# 00_POWER.net
KiCad netlist of a schematic drawn in Altium Designer
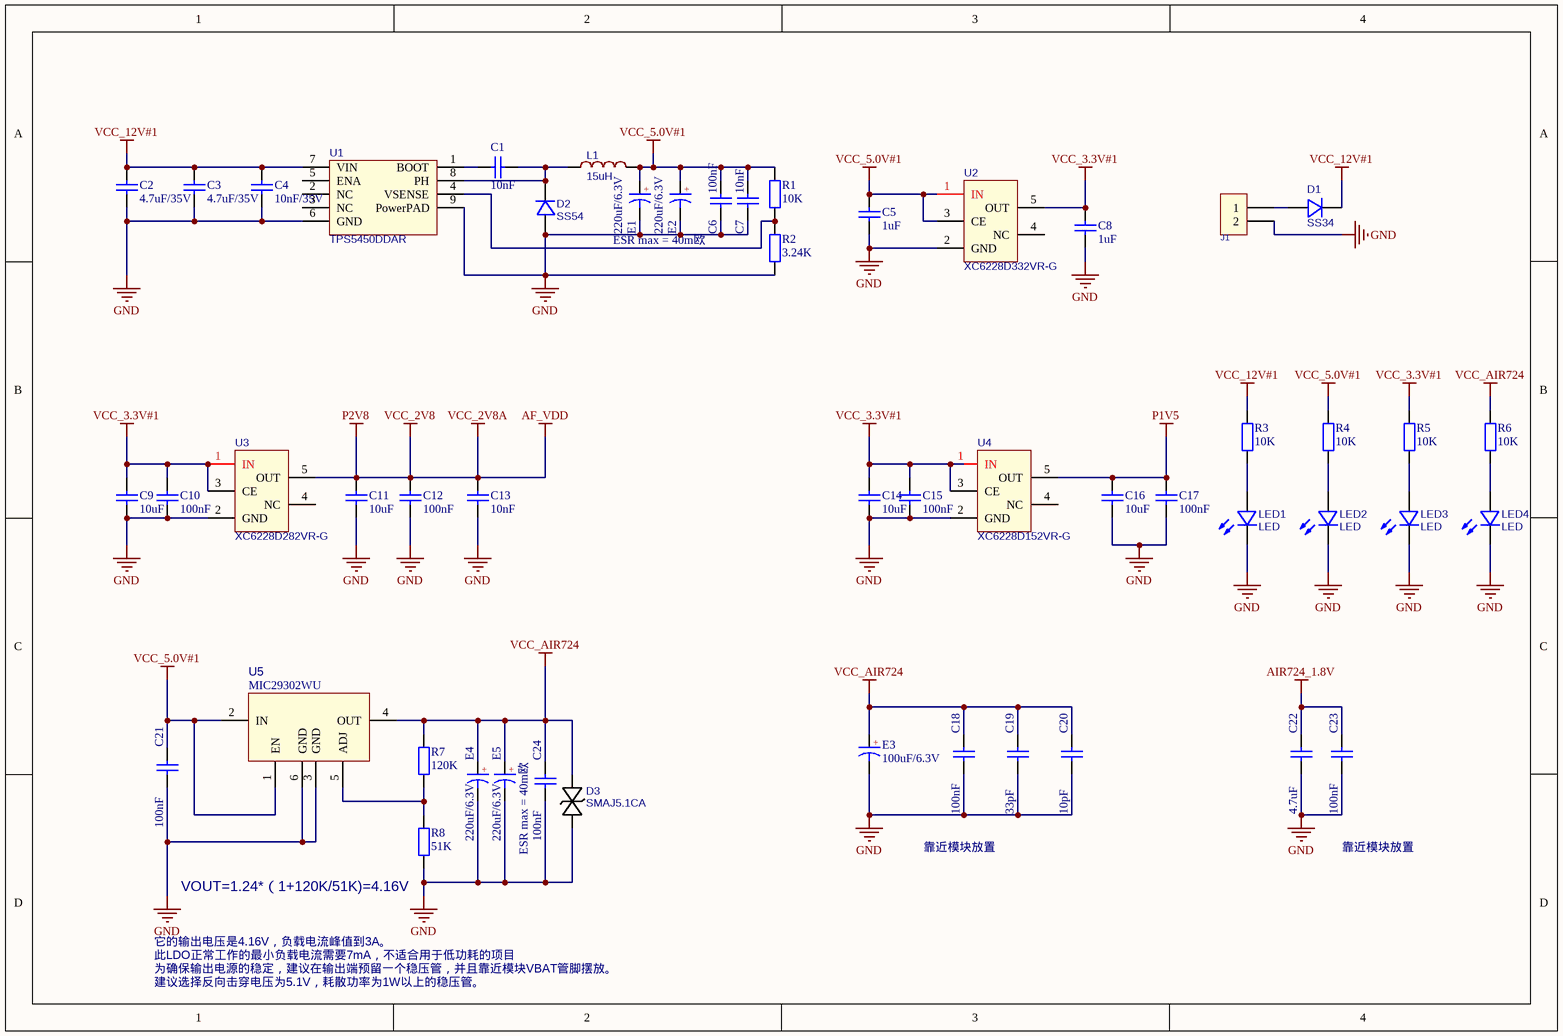
[diagram p0: 00_POWER.SchDoc]

(export (version "E")
  (design (tool "Eeschema 10.0.6"))
  (components
    (comp (ref "C1")
      (value "10nF")
      (footprint "0603-C")
      (description "贴片电容")
      (libsource (lib "封装库") (part "C"))
    )
    (comp (ref "C2")
      (value "4.7uF/35V")
      (footprint "0805-C")
      (description "贴片电容")
      (libsource (lib "封装库") (part "C"))
    )
    (comp (ref "C3")
      (value "4.7uF/35V")
      (footprint "0805-C")
      (description "贴片电容")
      (libsource (lib "封装库") (part "C"))
    )
    (comp (ref "C4")
      (value "10nF/35V")
      (footprint "0603-C")
      (description "贴片电容")
      (libsource (lib "封装库") (part "C"))
    )
    (comp (ref "C5")
      (value "1uF")
      (footprint "0603-C")
      (description "贴片电容")
      (libsource (lib "封装库") (part "C"))
    )
    (comp (ref "C6")
      (value "100nF")
      (footprint "0603-C")
      (description "贴片电容")
      (libsource (lib "封装库") (part "C"))
    )
    (comp (ref "C7")
      (value "10nF")
      (footprint "0603-C")
      (description "贴片电容")
      (libsource (lib "封装库") (part "C"))
    )
    (comp (ref "C8")
      (value "1uF")
      (footprint "0603-C")
      (description "贴片电容")
      (libsource (lib "封装库") (part "C"))
    )
    (comp (ref "C9")
      (value "10uF")
      (footprint "0603-C")
      (description "贴片电容")
      (libsource (lib "封装库") (part "C"))
    )
    (comp (ref "C10")
      (value "100nF")
      (footprint "0603-C")
      (description "贴片电容")
      (libsource (lib "封装库") (part "C"))
    )
    (comp (ref "C11")
      (value "10uF")
      (footprint "0603-C")
      (description "贴片电容")
      (libsource (lib "封装库") (part "C"))
    )
    (comp (ref "C12")
      (value "100nF")
      (footprint "0603-C")
      (description "贴片电容")
      (libsource (lib "封装库") (part "C"))
    )
    (comp (ref "C13")
      (value "10nF")
      (footprint "0603-C")
      (description "贴片电容")
      (libsource (lib "封装库") (part "C"))
    )
    (comp (ref "C14")
      (value "10uF")
      (footprint "0603-C")
      (description "贴片电容")
      (libsource (lib "封装库") (part "C"))
    )
    (comp (ref "C15")
      (value "100nF")
      (footprint "0603-C")
      (description "贴片电容")
      (libsource (lib "封装库") (part "C"))
    )
    (comp (ref "C16")
      (value "10uF")
      (footprint "0603-C")
      (description "贴片电容")
      (libsource (lib "封装库") (part "C"))
    )
    (comp (ref "C17")
      (value "100nF")
      (footprint "0603-C")
      (description "贴片电容")
      (libsource (lib "封装库") (part "C"))
    )
    (comp (ref "C18")
      (value "100nF")
      (footprint "0603-C")
      (description "贴片电容")
      (libsource (lib "封装库") (part "C"))
    )
    (comp (ref "C19")
      (value "33pF")
      (footprint "0603-C")
      (description "贴片电容")
      (libsource (lib "封装库") (part "C"))
    )
    (comp (ref "C20")
      (value "10pF")
      (footprint "0603-C")
      (description "贴片电容")
      (libsource (lib "封装库") (part "C"))
    )
    (comp (ref "C21")
      (value "100nF")
      (footprint "0603-C")
      (description "贴片电容")
      (libsource (lib "封装库") (part "C"))
    )
    (comp (ref "C22")
      (value "4.7uF")
      (footprint "0603-C")
      (description "贴片电容")
      (libsource (lib "封装库") (part "C"))
    )
    (comp (ref "C23")
      (value "100nF")
      (footprint "0603-C")
      (description "贴片电容")
      (libsource (lib "封装库") (part "C"))
    )
    (comp (ref "C24")
      (value "100nF")
      (footprint "0603-C")
      (description "贴片电容")
      (libsource (lib "封装库") (part "C"))
    )
    (comp (ref "D1")
      (value "SS34")
      (footprint "SS34-SMA")
      (fields
        (field (name "BOM_SUPPLIER PART") "C118334")
        (field (name "BOM_MANUFACTURER PART") "D-G060306G1-KS2")
        (field (name "CONTRIBUTOR") "LCSC")
      )
      (libsource (lib "封装库") (part "SS34"))
    )
    (comp (ref "D2")
      (value "SS54")
      (footprint "SS34-SMA")
      (fields
        (field (name "BOM_SUPPLIER PART") "C118334")
        (field (name "BOM_MANUFACTURER PART") "D-G060306G1-KS2")
        (field (name "CONTRIBUTOR") "LCSC")
      )
      (libsource (lib "封装库") (part "SS34"))
    )
    (comp (ref "D3")
      (value "SMAJ5.1CA")
      (footprint "ZENER")
      (description "SMAJ6.0CA_C698928")
      (fields
        (field (name "BOM_SUPPLIER PART") "C698928")
        (field (name "BOM_MANUFACTURER PART") "SMAJ6.0CA")
        (field (name "CONTRIBUTOR") "LCSC")
      )
      (libsource (lib "封装库") (part "SMAJ6.0CA"))
    )
    (comp (ref "E1")
      (value "220uF/6.3V")
      (footprint "CD B(3528)")
      (description "贴片钽电容")
      (libsource (lib "封装库") (part "CT"))
    )
    (comp (ref "E2")
      (value "220uF/6.3V")
      (footprint "CD B(3528)")
      (description "贴片钽电容")
      (libsource (lib "封装库") (part "CT"))
    )
    (comp (ref "E3")
      (value "100uF/6.3V")
      (footprint "CD B(3528)")
      (description "贴片钽电容")
      (libsource (lib "封装库") (part "CT"))
    )
    (comp (ref "E4")
      (value "220uF/6.3V")
      (footprint "CD B(3528)")
      (description "贴片钽电容")
      (libsource (lib "封装库") (part "CT"))
    )
    (comp (ref "E5")
      (value "220uF/6.3V")
      (footprint "CD B(3528)")
      (description "贴片钽电容")
      (libsource (lib "封装库") (part "CT"))
    )
    (comp (ref "J1")
      (value "KF128-5.0-2P")
      (footprint "KF128-5.0-2P")
      (fields (field (name "MANUFACTURER") "KEFA(科发)"))
      (libsource (lib "封装库") (part "KF128-5.0-2P"))
    )
    (comp (ref "L1")
      (value "15uH")
      (footprint "电感7*7*3")
      (description "L")
      (fields
        (field (name "BOM_MANUFACTURER PART") "UPZ2012D800-4R0TF")
        (field (name "BOM_SUPPLIER PART") "C145060")
        (field (name "CONTRIBUTOR") "LCSC")
      )
      (libsource (lib "封装库") (part "L"))
    )
    (comp (ref "LED1")
      (value "LED")
      (footprint "LED-0603")
      (fields
        (field (name "BOM_SUPPLIER PART") "C118334")
        (field (name "BOM_MANUFACTURER PART") "D-G060306G1-KS2")
        (field (name "CONTRIBUTOR") "LCSC")
      )
      (libsource (lib "封装库") (part "LED"))
    )
    (comp (ref "LED2")
      (value "LED")
      (footprint "LED-0603")
      (fields
        (field (name "BOM_SUPPLIER PART") "C118334")
        (field (name "BOM_MANUFACTURER PART") "D-G060306G1-KS2")
        (field (name "CONTRIBUTOR") "LCSC")
      )
      (libsource (lib "封装库") (part "LED"))
    )
    (comp (ref "LED3")
      (value "LED")
      (footprint "LED-0603")
      (fields
        (field (name "BOM_SUPPLIER PART") "C118334")
        (field (name "BOM_MANUFACTURER PART") "D-G060306G1-KS2")
        (field (name "CONTRIBUTOR") "LCSC")
      )
      (libsource (lib "封装库") (part "LED"))
    )
    (comp (ref "LED4")
      (value "LED")
      (footprint "LED-0603")
      (fields
        (field (name "BOM_SUPPLIER PART") "C118334")
        (field (name "BOM_MANUFACTURER PART") "D-G060306G1-KS2")
        (field (name "CONTRIBUTOR") "LCSC")
      )
      (libsource (lib "封装库") (part "LED"))
    )
    (comp (ref "R1")
      (value "10K")
      (footprint "0603-R")
      (description "贴片电阻")
      (libsource (lib "封装库") (part "R"))
    )
    (comp (ref "R2")
      (value "3.24K")
      (footprint "0603-R")
      (description "贴片电阻")
      (libsource (lib "封装库") (part "R"))
    )
    (comp (ref "R3")
      (value "10K")
      (footprint "0603-R")
      (description "贴片电阻")
      (libsource (lib "封装库") (part "R"))
    )
    (comp (ref "R4")
      (value "10K")
      (footprint "0603-R")
      (description "贴片电阻")
      (libsource (lib "封装库") (part "R"))
    )
    (comp (ref "R5")
      (value "10K")
      (footprint "0603-R")
      (description "贴片电阻")
      (libsource (lib "封装库") (part "R"))
    )
    (comp (ref "R6")
      (value "10K")
      (footprint "0603-R")
      (description "贴片电阻")
      (libsource (lib "封装库") (part "R"))
    )
    (comp (ref "R7")
      (value "120K")
      (footprint "0603-R")
      (description "贴片电阻")
      (libsource (lib "封装库") (part "R"))
    )
    (comp (ref "R8")
      (value "51K")
      (footprint "0603-R")
      (description "贴片电阻")
      (libsource (lib "封装库") (part "R"))
    )
    (comp (ref "U1")
      (value "TPS5450DDAR")
      (footprint "TPS5430")
      (fields (field (name "BOM_MANUFACTURER PART") "TPS5430DDAR") (field (name "BOM_SUPPLIER PART") "C9864"))
      (libsource (lib "封装库") (part "TPS5430DDAR"))
    )
    (comp (ref "U2")
      (value "XC6228D332VR-G")
      (footprint "XC6228D332VR-G")
      (fields (field (name "BOM_SUPPLIER PART") "C69841"))
      (libsource (lib "封装库") (part "XC6228D332VR-G"))
    )
    (comp (ref "U3")
      (value "XC6228D282VR-G")
      (footprint "XC6228D332VR-G")
      (fields
        (field (name "BOM_MANUFACTURER PART") "XC6228D332VR-G")
        (field (name "BOM_SUPPLIER PART") "C69841")
      )
      (libsource (lib "封装库") (part "XC6228D282VR-G"))
    )
    (comp (ref "U4")
      (value "XC6228D152VR-G")
      (footprint "XC6228D332VR-G")
      (fields
        (field (name "BOM_MANUFACTURER PART") "XC6228D332VR-G")
        (field (name "BOM_SUPPLIER PART") "C69841")
      )
      (libsource (lib "封装库") (part "XC6228D282VR-G"))
    )
    (comp (ref "U5")
      (value "MIC29302WU")
      (footprint "MIC29302WU")
      (fields (field (name "MANUFACTURER") "UMW(友台半导体)"))
      (libsource (lib "封装库") (part "MIC29302WU"))
    )
  )
  (nets
    (net (code "1") (name "AF_VDD") (class "Default")
      (node (ref "C11") (pin "2") (pinfunction "2_2") (pintype "passive"))
      (node (ref "C12") (pin "2") (pinfunction "2_2") (pintype "passive"))
      (node (ref "C13") (pin "2") (pinfunction "2_2") (pintype "passive"))
      (node (ref "U3") (pin "5") (pinfunction "OUT_5") (pintype "passive"))
    )
    (net (code "2") (name "AIR724_1.8V") (class "Default")
      (node (ref "C22") (pin "2") (pinfunction "2_2") (pintype "passive"))
      (node (ref "C23") (pin "2") (pinfunction "2_2") (pintype "passive"))
    )
    (net (code "3") (name "GND") (class "Default")
      (node (ref "C10") (pin "1") (pinfunction "1_1") (pintype "passive"))
      (node (ref "C11") (pin "1") (pinfunction "1_1") (pintype "passive"))
      (node (ref "C12") (pin "1") (pinfunction "1_1") (pintype "passive"))
      (node (ref "C13") (pin "1") (pinfunction "1_1") (pintype "passive"))
      (node (ref "C14") (pin "1") (pinfunction "1_1") (pintype "passive"))
      (node (ref "C15") (pin "1") (pinfunction "1_1") (pintype "passive"))
      (node (ref "C16") (pin "1") (pinfunction "1_1") (pintype "passive"))
      (node (ref "C17") (pin "1") (pinfunction "1_1") (pintype "passive"))
      (node (ref "C18") (pin "1") (pinfunction "1_1") (pintype "passive"))
      (node (ref "C19") (pin "1") (pinfunction "1_1") (pintype "passive"))
      (node (ref "C2") (pin "2") (pinfunction "2_2") (pintype "passive"))
      (node (ref "C20") (pin "1") (pinfunction "1_1") (pintype "passive"))
      (node (ref "C21") (pin "1") (pinfunction "1_1") (pintype "passive"))
      (node (ref "C22") (pin "1") (pinfunction "1_1") (pintype "passive"))
      (node (ref "C23") (pin "1") (pinfunction "1_1") (pintype "passive"))
      (node (ref "C24") (pin "1") (pinfunction "1_1") (pintype "passive"))
      (node (ref "C3") (pin "2") (pinfunction "2_2") (pintype "passive"))
      (node (ref "C4") (pin "1") (pinfunction "1_1") (pintype "passive"))
      (node (ref "C5") (pin "1") (pinfunction "1_1") (pintype "passive"))
      (node (ref "C6") (pin "2") (pinfunction "2_2") (pintype "passive"))
      (node (ref "C7") (pin "2") (pinfunction "2_2") (pintype "passive"))
      (node (ref "C8") (pin "1") (pinfunction "1_1") (pintype "passive"))
      (node (ref "C9") (pin "1") (pinfunction "1_1") (pintype "passive"))
      (node (ref "D2") (pin "1") (pinfunction "+_1") (pintype "passive"))
      (node (ref "D3") (pin "2") (pinfunction "A_2") (pintype "passive"))
      (node (ref "E1") (pin "2") (pinfunction "K_2") (pintype "passive"))
      (node (ref "E2") (pin "2") (pinfunction "K_2") (pintype "passive"))
      (node (ref "E3") (pin "2") (pinfunction "K_2") (pintype "passive"))
      (node (ref "E4") (pin "2") (pinfunction "K_2") (pintype "passive"))
      (node (ref "E5") (pin "2") (pinfunction "K_2") (pintype "passive"))
      (node (ref "J1") (pin "2") (pinfunction "2_2") (pintype "passive"))
      (node (ref "LED1") (pin "1") (pinfunction "-_1") (pintype "passive"))
      (node (ref "LED2") (pin "1") (pinfunction "-_1") (pintype "passive"))
      (node (ref "LED3") (pin "1") (pinfunction "-_1") (pintype "passive"))
      (node (ref "LED4") (pin "1") (pinfunction "-_1") (pintype "passive"))
      (node (ref "R2") (pin "2") (pinfunction "2_2") (pintype "passive"))
      (node (ref "R8") (pin "2") (pinfunction "2_2") (pintype "passive"))
      (node (ref "U1") (pin "6") (pinfunction "GND_6") (pintype "passive"))
      (node (ref "U1") (pin "9") (pinfunction "PowerPAD_9") (pintype "passive"))
      (node (ref "U2") (pin "2") (pinfunction "GND_2") (pintype "passive"))
      (node (ref "U3") (pin "2") (pinfunction "GND_2") (pintype "passive"))
      (node (ref "U4") (pin "2") (pinfunction "GND_2") (pintype "passive"))
      (node (ref "U5") (pin "3") (pinfunction "GND_3") (pintype "passive"))
      (node (ref "U5") (pin "6") (pinfunction "GND_6") (pintype "passive"))
    )
    (net (code "4") (name "Net-(D1-+)") (class "Default")
      (node (ref "D1") (pin "1") (pinfunction "+_1") (pintype "passive"))
      (node (ref "J1") (pin "1") (pinfunction "1_1") (pintype "passive"))
    )
    (net (code "5") (name "Net-(D2--)") (class "Default")
      (node (ref "C1") (pin "1") (pinfunction "1_1") (pintype "passive"))
      (node (ref "D2") (pin "2") (pinfunction "-_2") (pintype "passive"))
      (node (ref "L1") (pin "1") (pinfunction "1_1") (pintype "passive"))
      (node (ref "U1") (pin "8") (pinfunction "PH_8") (pintype "passive"))
    )
    (net (code "6") (name "Net-(LED1-+)") (class "Default")
      (node (ref "LED1") (pin "2") (pinfunction "+_2") (pintype "passive"))
      (node (ref "R3") (pin "1") (pinfunction "1_1") (pintype "passive"))
    )
    (net (code "7") (name "Net-(LED2-+)") (class "Default")
      (node (ref "LED2") (pin "2") (pinfunction "+_2") (pintype "passive"))
      (node (ref "R4") (pin "1") (pinfunction "1_1") (pintype "passive"))
    )
    (net (code "8") (name "Net-(LED3-+)") (class "Default")
      (node (ref "LED3") (pin "2") (pinfunction "+_2") (pintype "passive"))
      (node (ref "R5") (pin "1") (pinfunction "1_1") (pintype "passive"))
    )
    (net (code "9") (name "Net-(LED4-+)") (class "Default")
      (node (ref "LED4") (pin "2") (pinfunction "+_2") (pintype "passive"))
      (node (ref "R6") (pin "1") (pinfunction "1_1") (pintype "passive"))
    )
    (net (code "10") (name "Net-(U1-BOOT)") (class "Default")
      (node (ref "C1") (pin "2") (pinfunction "2_2") (pintype "passive"))
      (node (ref "U1") (pin "1") (pinfunction "BOOT_1") (pintype "passive"))
    )
    (net (code "11") (name "Net-(U1-VSENSE)") (class "Default")
      (node (ref "R1") (pin "2") (pinfunction "2_2") (pintype "passive"))
      (node (ref "R2") (pin "1") (pinfunction "1_1") (pintype "passive"))
      (node (ref "U1") (pin "4") (pinfunction "VSENSE_4") (pintype "passive"))
    )
    (net (code "12") (name "Net-(U5-ADJ)") (class "Default")
      (node (ref "R7") (pin "2") (pinfunction "2_2") (pintype "passive"))
      (node (ref "R8") (pin "1") (pinfunction "1_1") (pintype "passive"))
      (node (ref "U5") (pin "5") (pinfunction "ADJ_5") (pintype "passive"))
    )
    (net (code "13") (name "P1V5") (class "Default")
      (node (ref "C16") (pin "2") (pinfunction "2_2") (pintype "passive"))
      (node (ref "C17") (pin "2") (pinfunction "2_2") (pintype "passive"))
      (node (ref "U4") (pin "5") (pinfunction "OUT_5") (pintype "passive"))
    )
    (net (code "14") (name "VCC_3.3V#1") (class "Default")
      (node (ref "C10") (pin "2") (pinfunction "2_2") (pintype "passive"))
      (node (ref "C14") (pin "2") (pinfunction "2_2") (pintype "passive"))
      (node (ref "C15") (pin "2") (pinfunction "2_2") (pintype "passive"))
      (node (ref "C8") (pin "2") (pinfunction "2_2") (pintype "passive"))
      (node (ref "C9") (pin "2") (pinfunction "2_2") (pintype "passive"))
      (node (ref "R5") (pin "2") (pinfunction "2_2") (pintype "passive"))
      (node (ref "U2") (pin "5") (pinfunction "OUT_5") (pintype "passive"))
      (node (ref "U3") (pin "1") (pinfunction "IN_1") (pintype "passive"))
      (node (ref "U3") (pin "3") (pinfunction "CE_3") (pintype "passive"))
      (node (ref "U4") (pin "1") (pinfunction "IN_1") (pintype "passive"))
      (node (ref "U4") (pin "3") (pinfunction "CE_3") (pintype "passive"))
    )
    (net (code "15") (name "VCC_5.0V#1") (class "Default")
      (node (ref "C21") (pin "2") (pinfunction "2_2") (pintype "passive"))
      (node (ref "C5") (pin "2") (pinfunction "2_2") (pintype "passive"))
      (node (ref "C6") (pin "1") (pinfunction "1_1") (pintype "passive"))
      (node (ref "C7") (pin "1") (pinfunction "1_1") (pintype "passive"))
      (node (ref "E1") (pin "1") (pinfunction "A_1") (pintype "passive"))
      (node (ref "E2") (pin "1") (pinfunction "A_1") (pintype "passive"))
      (node (ref "L1") (pin "2") (pinfunction "2_2") (pintype "passive"))
      (node (ref "R1") (pin "1") (pinfunction "1_1") (pintype "passive"))
      (node (ref "R4") (pin "2") (pinfunction "2_2") (pintype "passive"))
      (node (ref "U2") (pin "1") (pinfunction "IN_1") (pintype "passive"))
      (node (ref "U2") (pin "3") (pinfunction "CE_3") (pintype "passive"))
      (node (ref "U5") (pin "1") (pinfunction "EN_1") (pintype "passive"))
      (node (ref "U5") (pin "2") (pinfunction "IN_2") (pintype "passive"))
    )
    (net (code "16") (name "VCC_12V#1") (class "Default")
      (node (ref "C2") (pin "1") (pinfunction "1_1") (pintype "passive"))
      (node (ref "C3") (pin "1") (pinfunction "1_1") (pintype "passive"))
      (node (ref "C4") (pin "2") (pinfunction "2_2") (pintype "passive"))
      (node (ref "D1") (pin "2") (pinfunction "-_2") (pintype "passive"))
      (node (ref "R3") (pin "2") (pinfunction "2_2") (pintype "passive"))
      (node (ref "U1") (pin "7") (pinfunction "VIN_7") (pintype "passive"))
    )
    (net (code "17") (name "VCC_AIR724") (class "Default")
      (node (ref "C18") (pin "2") (pinfunction "2_2") (pintype "passive"))
      (node (ref "C19") (pin "2") (pinfunction "2_2") (pintype "passive"))
      (node (ref "C20") (pin "2") (pinfunction "2_2") (pintype "passive"))
      (node (ref "C24") (pin "2") (pinfunction "2_2") (pintype "passive"))
      (node (ref "D3") (pin "1") (pinfunction "C_1") (pintype "passive"))
      (node (ref "E3") (pin "1") (pinfunction "A_1") (pintype "passive"))
      (node (ref "E4") (pin "1") (pinfunction "A_1") (pintype "passive"))
      (node (ref "E5") (pin "1") (pinfunction "A_1") (pintype "passive"))
      (node (ref "R6") (pin "2") (pinfunction "2_2") (pintype "passive"))
      (node (ref "R7") (pin "1") (pinfunction "1_1") (pintype "passive"))
      (node (ref "U5") (pin "4") (pinfunction "OUT_4") (pintype "passive"))
    )
    (net (code "18") (name "unconnected-(U1-ENA-Pad5)") (class "Default")
      (node (ref "U1") (pin "5") (pinfunction "ENA_5") (pintype "passive"))
    )
    (net (code "19") (name "unconnected-(U1-NC-Pad2)") (class "Default")
      (node (ref "U1") (pin "2") (pinfunction "NC_2") (pintype "passive"))
    )
    (net (code "20") (name "unconnected-(U1-NC-Pad3)") (class "Default")
      (node (ref "U1") (pin "3") (pinfunction "NC_3") (pintype "passive"))
    )
    (net (code "21") (name "unconnected-(U2-NC-Pad4)") (class "Default")
      (node (ref "U2") (pin "4") (pinfunction "NC_4") (pintype "passive"))
    )
    (net (code "22") (name "unconnected-(U3-NC-Pad4)") (class "Default")
      (node (ref "U3") (pin "4") (pinfunction "NC_4") (pintype "passive"))
    )
    (net (code "23") (name "unconnected-(U4-NC-Pad4)") (class "Default")
      (node (ref "U4") (pin "4") (pinfunction "NC_4") (pintype "passive"))
    )
  )
)
